# SH16_-_SPI_ROM.net
KiCad netlist of a schematic drawn in Altium Designer
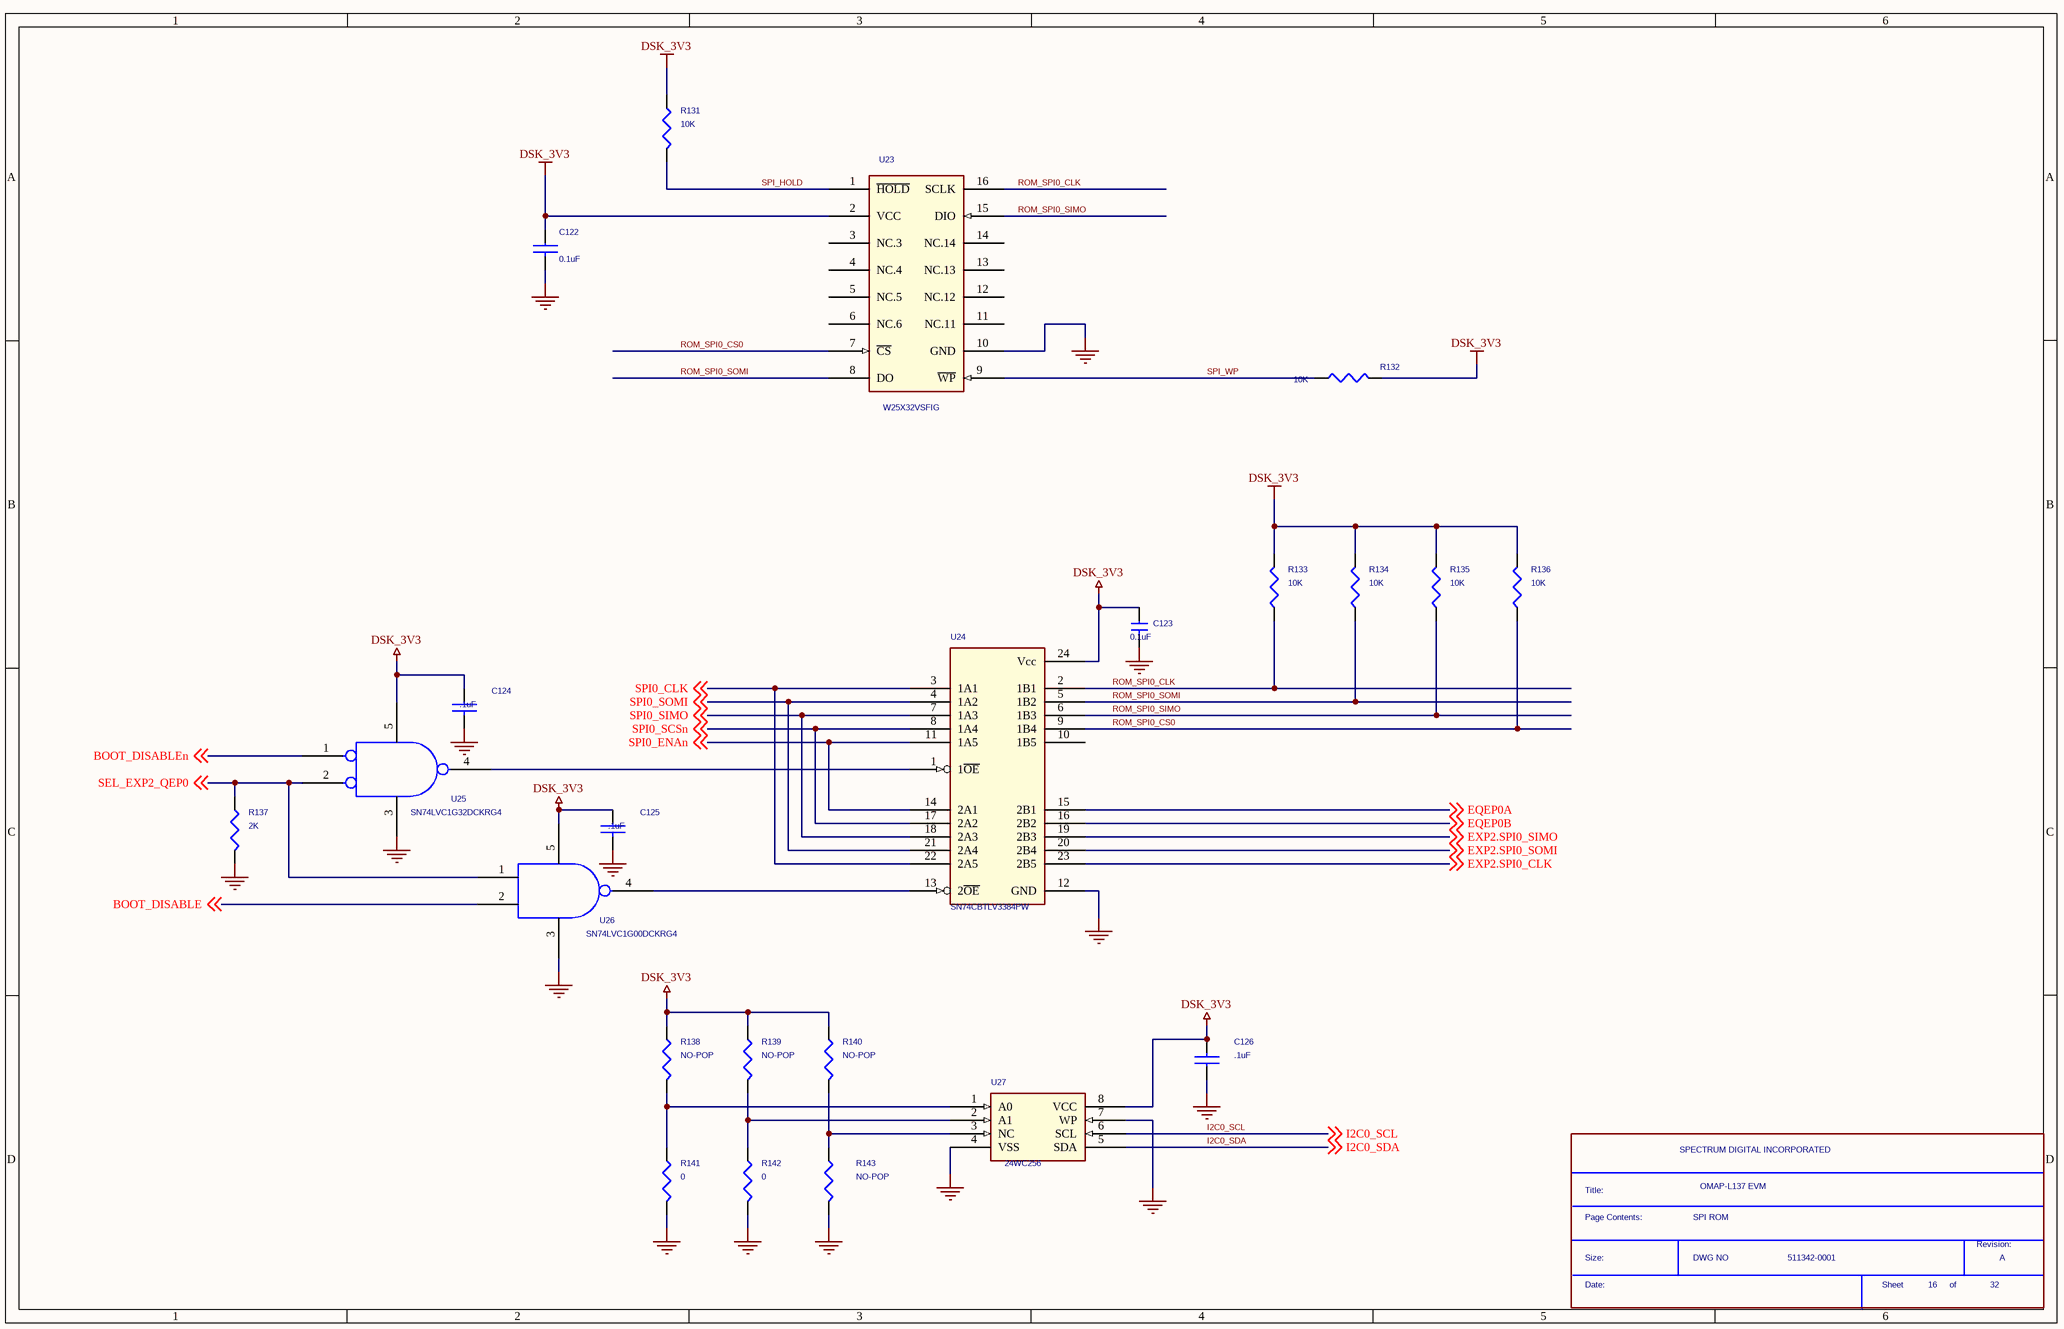
[diagram p0: SH16 - SPI ROM.SchDoc]

(export (version "E")
  (design (tool "Eeschema 10.0.6"))
  (components
    (comp (ref "C122")
      (value "0.1uF")
      (footprint "c402-25")
      (fields (field (name "PART #") "101587-1100R"))
      (libsource (lib "*") (part "CAP NP"))
    )
    (comp (ref "C123")
      (value "0.1uF")
      (footprint "c402-25")
      (fields (field (name "PART #") "101587-1100R"))
      (libsource (lib "*") (part "CAP NP_1"))
    )
    (comp (ref "C124")
      (value ".1uF")
      (footprint "c402-25")
      (fields (field (name "PART #") "101587-1100R"))
      (libsource (lib "*") (part "CAP NP_2"))
    )
    (comp (ref "C125")
      (value ".1uF")
      (footprint "c402-25")
      (fields (field (name "PART #") "101587-1100R"))
      (libsource (lib "*") (part "CAP NP_2"))
    )
    (comp (ref "C126")
      (value ".1uF")
      (footprint "C0603")
      (fields (field (name "PART #") "101587-1100R"))
      (libsource (lib "*") (part "CAP .1 uF 10% 0603"))
    )
    (comp (ref "R131")
      (value "10K")
      (footprint "r402-25")
      (fields (field (name "PART #") "101370-1003R"))
      (libsource (lib "*") (part "R"))
    )
    (comp (ref "R132")
      (value "10K")
      (footprint "r402-25")
      (fields (field (name "PART #") "101370-1003R"))
      (libsource (lib "*") (part "RESISTOR_1"))
    )
    (comp (ref "R133")
      (value "10K")
      (footprint "r402-25")
      (fields (field (name "PART #") "101370-1003R"))
      (libsource (lib "*") (part "RESISTOR_1"))
    )
    (comp (ref "R134")
      (value "10K")
      (footprint "r402-25")
      (fields (field (name "PART #") "101370-1003R"))
      (libsource (lib "*") (part "RESISTOR_1"))
    )
    (comp (ref "R135")
      (value "10K")
      (footprint "r402-25")
      (fields (field (name "PART #") "101370-1003R"))
      (libsource (lib "*") (part "RESISTOR_1"))
    )
    (comp (ref "R136")
      (value "10K")
      (footprint "r402-25")
      (fields (field (name "PART #") "101370-1003R"))
      (libsource (lib "*") (part "RESISTOR_1"))
    )
    (comp (ref "R137")
      (value "2K")
      (footprint "r402-25")
      (fields (field (name "PART #") "101370-2002R"))
      (libsource (lib "*") (part "R"))
    )
    (comp (ref "R138")
      (value "NO-POP")
      (footprint "r402-25")
      (fields (field (name "PART #") "R0402-NOPOP"))
      (libsource (lib "*") (part "R"))
    )
    (comp (ref "R139")
      (value "NO-POP")
      (footprint "r402-25")
      (fields (field (name "PART #") "R0402-NOPOP"))
      (libsource (lib "*") (part "R"))
    )
    (comp (ref "R140")
      (value "NO-POP")
      (footprint "r402-25")
      (fields (field (name "PART #") "R0402-NOPOP"))
      (libsource (lib "*") (part "R"))
    )
    (comp (ref "R141")
      (value "0")
      (footprint "r402-25")
      (fields (field (name "PART #") "101370-0001R"))
      (libsource (lib "*") (part "R_1"))
    )
    (comp (ref "R142")
      (value "0")
      (footprint "r402-25")
      (fields (field (name "PART #") "101370-0001R"))
      (libsource (lib "*") (part "R_1"))
    )
    (comp (ref "R143")
      (value "NO-POP")
      (footprint "r402-25")
      (fields (field (name "PART #") "R0402-NOPOP"))
      (libsource (lib "*") (part "R"))
    )
    (comp (ref "U23")
      (value "W25X32VSFIG")
      (footprint "so16-25x75-300")
      (fields (field (name "PART #") "102801-0001R"))
      (libsource (lib "*") (part "SPI_EEPROM_0"))
    )
    (comp (ref "U24")
      (value "SN74CBTLV3384PW")
      (footprint "TSSOP-24")
      (description "IC, Quad 2-to-1 Mux with Level Conversion")
      (fields (field (name "PART #") "101679-0001R") (field (name "MFG") "TI"))
      (libsource (lib "*") (part "SN74CBTD3384PW"))
    )
    (comp (ref "U25")
      (value "SN74LVC1G32DCKRG4")
      (footprint "dck-5")
      (fields (field (name "PART #") "101057-0032R"))
      (libsource (lib "*") (part "1g32neg"))
    )
    (comp (ref "U26")
      (value "SN74LVC1G00DCKRG4")
      (footprint "dck-5")
      (fields (field (name "PART #") "101057-0001R"))
      (libsource (lib "*") (part "1g00_0"))
    )
    (comp (ref "U27")
      (value "24WC256")
      (footprint "SOIC")
      (description "256K-Bit I 2 C Serial CMOS EEPROM")
      (fields (field (name "PART #") "102235-0001R"))
      (libsource (lib "*") (part "24WC256"))
    )
  )
  (nets
    (net (code "1") (name "/ROM_SPI0_CLK") (class "Default")
      (node (ref "R133") (pin "1") (pinfunction "1_1") (pintype "passive"))
      (node (ref "U23") (pin "16") (pinfunction "SCLK_16") (pintype "passive"))
      (node (ref "U24") (pin "2") (pinfunction "1B1_2") (pintype "passive"))
    )
    (net (code "2") (name "/ROM_SPI0_CS0") (class "Default")
      (node (ref "R136") (pin "1") (pinfunction "1_1") (pintype "passive"))
      (node (ref "U23") (pin "7") (pinfunction "~{CS}_7") (pintype "input"))
      (node (ref "U24") (pin "9") (pinfunction "1B4_9") (pintype "passive"))
    )
    (net (code "3") (name "/ROM_SPI0_SIMO") (class "Default")
      (node (ref "R135") (pin "1") (pinfunction "1_1") (pintype "passive"))
      (node (ref "U23") (pin "15") (pinfunction "DIO_15") (pintype "input"))
      (node (ref "U24") (pin "6") (pinfunction "1B3_6") (pintype "passive"))
    )
    (net (code "4") (name "/ROM_SPI0_SOMI") (class "Default")
      (node (ref "R134") (pin "1") (pinfunction "1_1") (pintype "passive"))
      (node (ref "U23") (pin "8") (pinfunction "DO_8") (pintype "passive"))
      (node (ref "U24") (pin "5") (pinfunction "1B2_5") (pintype "passive"))
    )
    (net (code "5") (name "/SPI_HOLD") (class "Default")
      (node (ref "R131") (pin "2") (pinfunction "2_2") (pintype "passive"))
      (node (ref "U23") (pin "1") (pinfunction "~{HOLD}_1") (pintype "passive"))
    )
    (net (code "6") (name "/SPI_WP") (class "Default")
      (node (ref "R132") (pin "2") (pinfunction "2_2") (pintype "passive"))
      (node (ref "U23") (pin "9") (pinfunction "~{WP}_9") (pintype "input"))
    )
    (net (code "7") (name "BOOT_DISABLE") (class "Default")
      (node (ref "U26") (pin "2") (pinfunction "B_2") (pintype "passive"))
    )
    (net (code "8") (name "BOOT_DISABLEn") (class "Default")
      (node (ref "U25") (pin "1") (pinfunction "A_1") (pintype "passive"))
    )
    (net (code "9") (name "DSK_3V3") (class "Default")
      (node (ref "C122") (pin "1") (pinfunction "1_1") (pintype "passive"))
      (node (ref "C123") (pin "1") (pinfunction "1_1") (pintype "passive"))
      (node (ref "C124") (pin "1") (pinfunction "1_1") (pintype "passive"))
      (node (ref "C125") (pin "1") (pinfunction "1_1") (pintype "passive"))
      (node (ref "C126") (pin "2") (pinfunction "2_2") (pintype "passive"))
      (node (ref "R131") (pin "1") (pinfunction "1_1") (pintype "passive"))
      (node (ref "R132") (pin "1") (pinfunction "1_1") (pintype "passive"))
      (node (ref "R133") (pin "2") (pinfunction "2_2") (pintype "passive"))
      (node (ref "R134") (pin "2") (pinfunction "2_2") (pintype "passive"))
      (node (ref "R135") (pin "2") (pinfunction "2_2") (pintype "passive"))
      (node (ref "R136") (pin "2") (pinfunction "2_2") (pintype "passive"))
      (node (ref "R138") (pin "1") (pinfunction "1_1") (pintype "passive"))
      (node (ref "R139") (pin "1") (pinfunction "1_1") (pintype "passive"))
      (node (ref "R140") (pin "1") (pinfunction "1_1") (pintype "passive"))
      (node (ref "U23") (pin "2") (pinfunction "VCC_2") (pintype "power_in"))
      (node (ref "U24") (pin "24") (pinfunction "Vcc_24") (pintype "power_in"))
      (node (ref "U25") (pin "5") (pinfunction "VCC_5") (pintype "passive"))
      (node (ref "U26") (pin "5") (pinfunction "VCC_5") (pintype "passive"))
      (node (ref "U27") (pin "8") (pinfunction "VCC_8") (pintype "passive"))
    )
    (net (code "10") (name "EQEP0A") (class "Default")
      (node (ref "U24") (pin "15") (pinfunction "2B1_15") (pintype "passive"))
    )
    (net (code "11") (name "EQEP0B") (class "Default")
      (node (ref "U24") (pin "16") (pinfunction "2B2_16") (pintype "passive"))
    )
    (net (code "12") (name "EXP2.SPI0_CLK") (class "Default")
      (node (ref "U24") (pin "23") (pinfunction "2B5_23") (pintype "passive"))
    )
    (net (code "13") (name "EXP2.SPI0_SIMO") (class "Default")
      (node (ref "U24") (pin "19") (pinfunction "2B3_19") (pintype "passive"))
    )
    (net (code "14") (name "EXP2.SPI0_SOMI") (class "Default")
      (node (ref "U24") (pin "20") (pinfunction "2B4_20") (pintype "passive"))
    )
    (net (code "15") (name "GND") (class "Default")
      (node (ref "C122") (pin "2") (pinfunction "2_2") (pintype "passive"))
      (node (ref "C123") (pin "2") (pinfunction "2_2") (pintype "passive"))
      (node (ref "C124") (pin "2") (pinfunction "2_2") (pintype "passive"))
      (node (ref "C125") (pin "2") (pinfunction "2_2") (pintype "passive"))
      (node (ref "C126") (pin "1") (pinfunction "1_1") (pintype "passive"))
      (node (ref "R137") (pin "2") (pinfunction "2_2") (pintype "passive"))
      (node (ref "R141") (pin "2") (pinfunction "2_2") (pintype "passive"))
      (node (ref "R142") (pin "2") (pinfunction "2_2") (pintype "passive"))
      (node (ref "R143") (pin "2") (pinfunction "2_2") (pintype "passive"))
      (node (ref "U23") (pin "10") (pinfunction "GND_10") (pintype "power_in"))
      (node (ref "U24") (pin "12") (pinfunction "GND_12") (pintype "power_in"))
      (node (ref "U25") (pin "3") (pinfunction "GND_3") (pintype "passive"))
      (node (ref "U26") (pin "3") (pinfunction "GND_3") (pintype "passive"))
      (node (ref "U27") (pin "4") (pinfunction "VSS_4") (pintype "passive"))
      (node (ref "U27") (pin "7") (pinfunction "WP_7") (pintype "input"))
    )
    (net (code "16") (name "I2C0_SCL") (class "Default")
      (node (ref "U27") (pin "6") (pinfunction "SCL_6") (pintype "input"))
    )
    (net (code "17") (name "I2C0_SDA") (class "Default")
      (node (ref "U27") (pin "5") (pinfunction "SDA_5") (pintype "passive"))
    )
    (net (code "18") (name "Net-(U24-1~{OE})") (class "Default")
      (node (ref "U24") (pin "1") (pinfunction "1~{OE}_1") (pintype "input"))
      (node (ref "U25") (pin "4") (pinfunction "Y_4") (pintype "passive"))
    )
    (net (code "19") (name "Net-(U24-2~{OE})") (class "Default")
      (node (ref "U24") (pin "13") (pinfunction "2~{OE}_13") (pintype "input"))
      (node (ref "U26") (pin "4") (pinfunction "Y_4") (pintype "passive"))
    )
    (net (code "20") (name "Net-(U27-A0)") (class "Default")
      (node (ref "R138") (pin "2") (pinfunction "2_2") (pintype "passive"))
      (node (ref "R141") (pin "1") (pinfunction "1_1") (pintype "passive"))
      (node (ref "U27") (pin "1") (pinfunction "A0_1") (pintype "input"))
    )
    (net (code "21") (name "Net-(U27-A1)") (class "Default")
      (node (ref "R139") (pin "2") (pinfunction "2_2") (pintype "passive"))
      (node (ref "R142") (pin "1") (pinfunction "1_1") (pintype "passive"))
      (node (ref "U27") (pin "2") (pinfunction "A1_2") (pintype "input"))
    )
    (net (code "22") (name "Net-(U27-NC)") (class "Default")
      (node (ref "R140") (pin "2") (pinfunction "2_2") (pintype "passive"))
      (node (ref "R143") (pin "1") (pinfunction "1_1") (pintype "passive"))
      (node (ref "U27") (pin "3") (pinfunction "NC_3") (pintype "input"))
    )
    (net (code "23") (name "SEL_EXP2_QEP0") (class "Default")
      (node (ref "R137") (pin "1") (pinfunction "1_1") (pintype "passive"))
      (node (ref "U25") (pin "2") (pinfunction "B_2") (pintype "passive"))
      (node (ref "U26") (pin "1") (pinfunction "A_1") (pintype "passive"))
    )
    (net (code "24") (name "SPI0_CLK") (class "Default")
      (node (ref "U24") (pin "22") (pinfunction "2A5_22") (pintype "passive"))
      (node (ref "U24") (pin "3") (pinfunction "1A1_3") (pintype "passive"))
    )
    (net (code "25") (name "SPI0_ENAn") (class "Default")
      (node (ref "U24") (pin "11") (pinfunction "1A5_11") (pintype "passive"))
      (node (ref "U24") (pin "14") (pinfunction "2A1_14") (pintype "passive"))
    )
    (net (code "26") (name "SPI0_SCSn") (class "Default")
      (node (ref "U24") (pin "17") (pinfunction "2A2_17") (pintype "passive"))
      (node (ref "U24") (pin "8") (pinfunction "1A4_8") (pintype "passive"))
    )
    (net (code "27") (name "SPI0_SIMO") (class "Default")
      (node (ref "U24") (pin "18") (pinfunction "2A3_18") (pintype "passive"))
      (node (ref "U24") (pin "7") (pinfunction "1A3_7") (pintype "passive"))
    )
    (net (code "28") (name "SPI0_SOMI") (class "Default")
      (node (ref "U24") (pin "21") (pinfunction "2A4_21") (pintype "passive"))
      (node (ref "U24") (pin "4") (pinfunction "1A2_4") (pintype "passive"))
    )
    (net (code "29") (name "unconnected-(U23-NC.3-Pad3)") (class "Default")
      (node (ref "U23") (pin "3") (pinfunction "NC.3_3") (pintype "passive"))
    )
    (net (code "30") (name "unconnected-(U23-NC.4-Pad4)") (class "Default")
      (node (ref "U23") (pin "4") (pinfunction "NC.4_4") (pintype "passive"))
    )
    (net (code "31") (name "unconnected-(U23-NC.5-Pad5)") (class "Default")
      (node (ref "U23") (pin "5") (pinfunction "NC.5_5") (pintype "passive"))
    )
    (net (code "32") (name "unconnected-(U23-NC.6-Pad6)") (class "Default")
      (node (ref "U23") (pin "6") (pinfunction "NC.6_6") (pintype "passive"))
    )
    (net (code "33") (name "unconnected-(U23-NC.11-Pad11)") (class "Default")
      (node (ref "U23") (pin "11") (pinfunction "NC.11_11") (pintype "passive"))
    )
    (net (code "34") (name "unconnected-(U23-NC.12-Pad12)") (class "Default")
      (node (ref "U23") (pin "12") (pinfunction "NC.12_12") (pintype "passive"))
    )
    (net (code "35") (name "unconnected-(U23-NC.13-Pad13)") (class "Default")
      (node (ref "U23") (pin "13") (pinfunction "NC.13_13") (pintype "passive"))
    )
    (net (code "36") (name "unconnected-(U23-NC.14-Pad14)") (class "Default")
      (node (ref "U23") (pin "14") (pinfunction "NC.14_14") (pintype "passive"))
    )
    (net (code "37") (name "unconnected-(U24-1B5-Pad10)") (class "Default")
      (node (ref "U24") (pin "10") (pinfunction "1B5_10") (pintype "passive"))
    )
  )
)
